# mainbrd.net
KiCad netlist of a schematic drawn in EAGLE
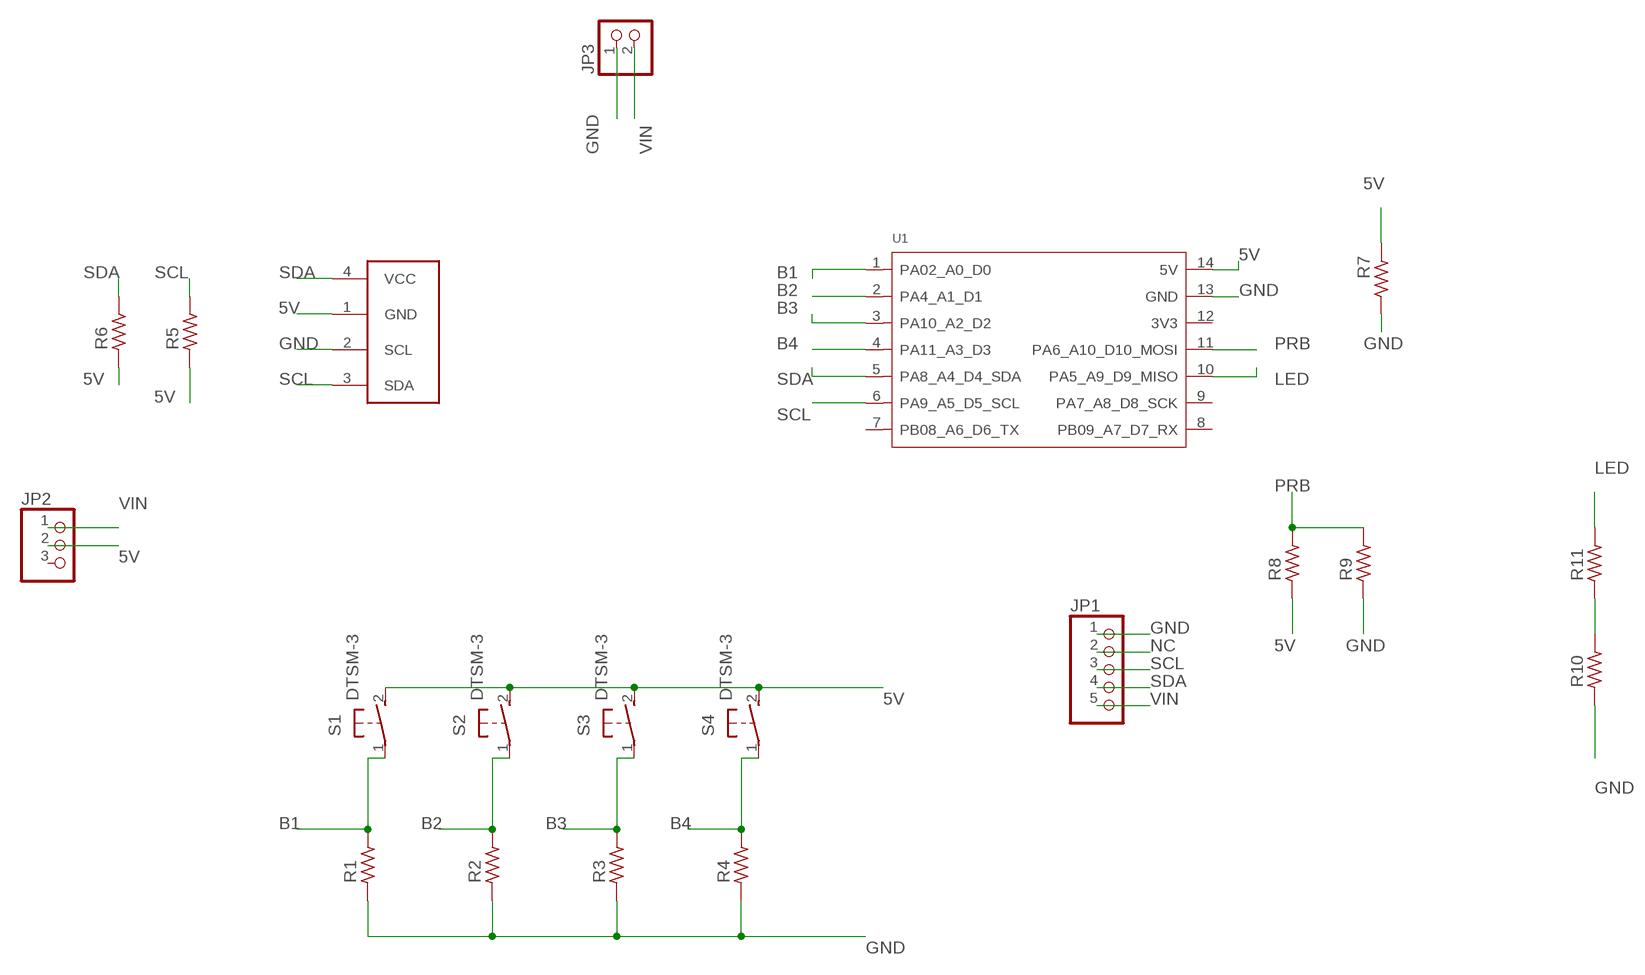
[diagram p0: schematic, sheet 1]

(export (version "E")
  (design (tool "Eeschema 10.0.6"))
  (components
    (comp (ref "JP1")
      (value "PINHD-1X5")
      (footprint "eagle-import:1X05")
      (libsource (lib "eagle-import") (part "PINHD-1X5"))
    )
    (comp (ref "JP2")
      (value "PINHD-1X3")
      (footprint "eagle-import:1X03")
      (libsource (lib "eagle-import") (part "PINHD-1X3"))
    )
    (comp (ref "JP3")
      (value "PINHD-1X2")
      (footprint "eagle-import:1X02")
      (libsource (lib "eagle-import") (part "PINHD-1X2"))
    )
    (comp (ref "R1")
      (value "R_1206")
      (footprint "eagle-import:R1206")
      (libsource (lib "eagle-import") (part "R_1206"))
    )
    (comp (ref "R2")
      (value "R_1206")
      (footprint "eagle-import:R1206")
      (libsource (lib "eagle-import") (part "R_1206"))
    )
    (comp (ref "R3")
      (value "R_1206")
      (footprint "eagle-import:R1206")
      (libsource (lib "eagle-import") (part "R_1206"))
    )
    (comp (ref "R4")
      (value "R_1206")
      (footprint "eagle-import:R1206")
      (libsource (lib "eagle-import") (part "R_1206"))
    )
    (comp (ref "R5")
      (value "R_1206")
      (footprint "eagle-import:R1206")
      (libsource (lib "eagle-import") (part "R_1206"))
    )
    (comp (ref "R6")
      (value "R_1206")
      (footprint "eagle-import:R1206")
      (libsource (lib "eagle-import") (part "R_1206"))
    )
    (comp (ref "R7")
      (value "R_1206")
      (footprint "eagle-import:R1206")
      (libsource (lib "eagle-import") (part "R_1206"))
    )
    (comp (ref "R8")
      (value "R_1206")
      (footprint "eagle-import:R1206")
      (libsource (lib "eagle-import") (part "R_1206"))
    )
    (comp (ref "R9")
      (value "R_1206")
      (footprint "eagle-import:R1206")
      (libsource (lib "eagle-import") (part "R_1206"))
    )
    (comp (ref "R10")
      (value "R_1206")
      (footprint "eagle-import:R1206")
      (libsource (lib "eagle-import") (part "R_1206"))
    )
    (comp (ref "R11")
      (value "R_1206")
      (footprint "eagle-import:R1206")
      (libsource (lib "eagle-import") (part "R_1206"))
    )
    (comp (ref "S1")
      (value "DTSM-3")
      (footprint "eagle-import:DTSM-3")
      (libsource (lib "eagle-import") (part "DTSM-3"))
    )
    (comp (ref "S2")
      (value "DTSM-3")
      (footprint "eagle-import:DTSM-3")
      (libsource (lib "eagle-import") (part "DTSM-3"))
    )
    (comp (ref "S3")
      (value "DTSM-3")
      (footprint "eagle-import:DTSM-3")
      (libsource (lib "eagle-import") (part "DTSM-3"))
    )
    (comp (ref "S4")
      (value "DTSM-3")
      (footprint "eagle-import:DTSM-3")
      (libsource (lib "eagle-import") (part "DTSM-3"))
    )
    (comp (ref "U$1")
      (value "I2C_OLED")
      (footprint "eagle-import:I2C_OLED_PACKAGE")
      (libsource (lib "eagle-import") (part "I2C_OLED"))
    )
    (comp (ref "U1")
      (value "MOUDLE-SEEEDUINO-XIAO")
      (footprint "eagle-import:MOUDLE14P-2.54-21X17.8MM")
      (libsource (lib "eagle-import") (part "MOUDLE-SEEEDUINO-XIAO"))
    )
  )
  (nets
    (net (code "1") (name "/5V") (class "Default")
      (node (ref "JP2") (pin "2") (pinfunction "2_2") (pintype "passive"))
      (node (ref "R5") (pin "1") (pinfunction "1_1") (pintype "passive"))
      (node (ref "R6") (pin "1") (pinfunction "1_1") (pintype "passive"))
      (node (ref "R7") (pin "2") (pinfunction "2_2") (pintype "passive"))
      (node (ref "R8") (pin "1") (pinfunction "1_1") (pintype "passive"))
      (node (ref "S1") (pin "2") (pinfunction "2_2") (pintype "passive"))
      (node (ref "S2") (pin "2") (pinfunction "2_2") (pintype "passive"))
      (node (ref "S3") (pin "2") (pinfunction "2_2") (pintype "passive"))
      (node (ref "S4") (pin "2") (pinfunction "2_2") (pintype "passive"))
      (node (ref "U$1") (pin "1") (pinfunction "GND_1") (pintype "bidirectional"))
      (node (ref "U1") (pin "14") (pinfunction "5V_14") (pintype "bidirectional"))
    )
    (net (code "2") (name "/B1") (class "Default")
      (node (ref "R1") (pin "2") (pinfunction "2_2") (pintype "passive"))
      (node (ref "S1") (pin "1") (pinfunction "1_1") (pintype "passive"))
      (node (ref "U1") (pin "1") (pinfunction "PA02_A0_D0_1") (pintype "bidirectional"))
    )
    (net (code "3") (name "/B2") (class "Default")
      (node (ref "R2") (pin "2") (pinfunction "2_2") (pintype "passive"))
      (node (ref "S2") (pin "1") (pinfunction "1_1") (pintype "passive"))
      (node (ref "U1") (pin "2") (pinfunction "PA4_A1_D1_2") (pintype "bidirectional"))
    )
    (net (code "4") (name "/B3") (class "Default")
      (node (ref "R3") (pin "2") (pinfunction "2_2") (pintype "passive"))
      (node (ref "S3") (pin "1") (pinfunction "1_1") (pintype "passive"))
      (node (ref "U1") (pin "3") (pinfunction "PA10_A2_D2_3") (pintype "bidirectional"))
    )
    (net (code "5") (name "/B4") (class "Default")
      (node (ref "R4") (pin "2") (pinfunction "2_2") (pintype "passive"))
      (node (ref "S4") (pin "1") (pinfunction "1_1") (pintype "passive"))
      (node (ref "U1") (pin "4") (pinfunction "PA11_A3_D3_4") (pintype "bidirectional"))
    )
    (net (code "6") (name "/GND") (class "Default")
      (node (ref "JP1") (pin "1") (pinfunction "1_1") (pintype "passive"))
      (node (ref "JP3") (pin "1") (pinfunction "1_1") (pintype "passive"))
      (node (ref "R1") (pin "1") (pinfunction "1_1") (pintype "passive"))
      (node (ref "R10") (pin "1") (pinfunction "1_1") (pintype "passive"))
      (node (ref "R2") (pin "1") (pinfunction "1_1") (pintype "passive"))
      (node (ref "R3") (pin "1") (pinfunction "1_1") (pintype "passive"))
      (node (ref "R4") (pin "1") (pinfunction "1_1") (pintype "passive"))
      (node (ref "R7") (pin "1") (pinfunction "1_1") (pintype "passive"))
      (node (ref "R9") (pin "1") (pinfunction "1_1") (pintype "passive"))
      (node (ref "U$1") (pin "2") (pinfunction "SCL_2") (pintype "bidirectional"))
      (node (ref "U1") (pin "13") (pinfunction "GND_13") (pintype "bidirectional"))
    )
    (net (code "7") (name "/LED") (class "Default")
      (node (ref "R11") (pin "2") (pinfunction "2_2") (pintype "passive"))
      (node (ref "U1") (pin "10") (pinfunction "PA5_A9_D9_MISO_10") (pintype "bidirectional"))
    )
    (net (code "8") (name "/NC") (class "Default")
      (node (ref "JP1") (pin "2") (pinfunction "2_2") (pintype "passive"))
    )
    (net (code "9") (name "/PRB") (class "Default")
      (node (ref "R8") (pin "2") (pinfunction "2_2") (pintype "passive"))
      (node (ref "R9") (pin "2") (pinfunction "2_2") (pintype "passive"))
      (node (ref "U1") (pin "11") (pinfunction "PA6_A10_D10_MOSI_11") (pintype "bidirectional"))
    )
    (net (code "10") (name "/SCL") (class "Default")
      (node (ref "JP1") (pin "3") (pinfunction "3_3") (pintype "passive"))
      (node (ref "R5") (pin "2") (pinfunction "2_2") (pintype "passive"))
      (node (ref "U$1") (pin "3") (pinfunction "SDA_3") (pintype "bidirectional"))
      (node (ref "U1") (pin "6") (pinfunction "PA9_A5_D5_SCL_6") (pintype "bidirectional"))
    )
    (net (code "11") (name "/SDA") (class "Default")
      (node (ref "JP1") (pin "4") (pinfunction "4_4") (pintype "passive"))
      (node (ref "R6") (pin "2") (pinfunction "2_2") (pintype "passive"))
      (node (ref "U$1") (pin "4") (pinfunction "VCC_4") (pintype "bidirectional"))
      (node (ref "U1") (pin "5") (pinfunction "PA8_A4_D4_SDA_5") (pintype "bidirectional"))
    )
    (net (code "12") (name "/VIN") (class "Default")
      (node (ref "JP1") (pin "5") (pinfunction "5_5") (pintype "passive"))
      (node (ref "JP2") (pin "1") (pinfunction "1_1") (pintype "passive"))
      (node (ref "JP3") (pin "2") (pinfunction "2_2") (pintype "passive"))
    )
    (net (code "13") (name "Net-(R10-Pad2)") (class "Default")
      (node (ref "R10") (pin "2") (pinfunction "2_2") (pintype "passive"))
      (node (ref "R11") (pin "1") (pinfunction "1_1") (pintype "passive"))
    )
    (net (code "14") (name "unconnected-(JP2-Pad3)") (class "Default")
      (node (ref "JP2") (pin "3") (pinfunction "3_3") (pintype "passive"))
    )
    (net (code "15") (name "unconnected-(U1-3V3-Pad12)") (class "Default")
      (node (ref "U1") (pin "12") (pinfunction "3V3_12") (pintype "bidirectional"))
    )
    (net (code "16") (name "unconnected-(U1-PA7_A8_D8_SCK-Pad9)") (class "Default")
      (node (ref "U1") (pin "9") (pinfunction "PA7_A8_D8_SCK_9") (pintype "bidirectional"))
    )
    (net (code "17") (name "unconnected-(U1-PB08_A6_D6_TX-Pad7)") (class "Default")
      (node (ref "U1") (pin "7") (pinfunction "PB08_A6_D6_TX_7") (pintype "bidirectional"))
    )
    (net (code "18") (name "unconnected-(U1-PB09_A7_D7_RX-Pad8)") (class "Default")
      (node (ref "U1") (pin "8") (pinfunction "PB09_A7_D7_RX_8") (pintype "bidirectional"))
    )
  )
)
